# Output_channel.net
KiCad netlist of a schematic drawn in Altium Designer
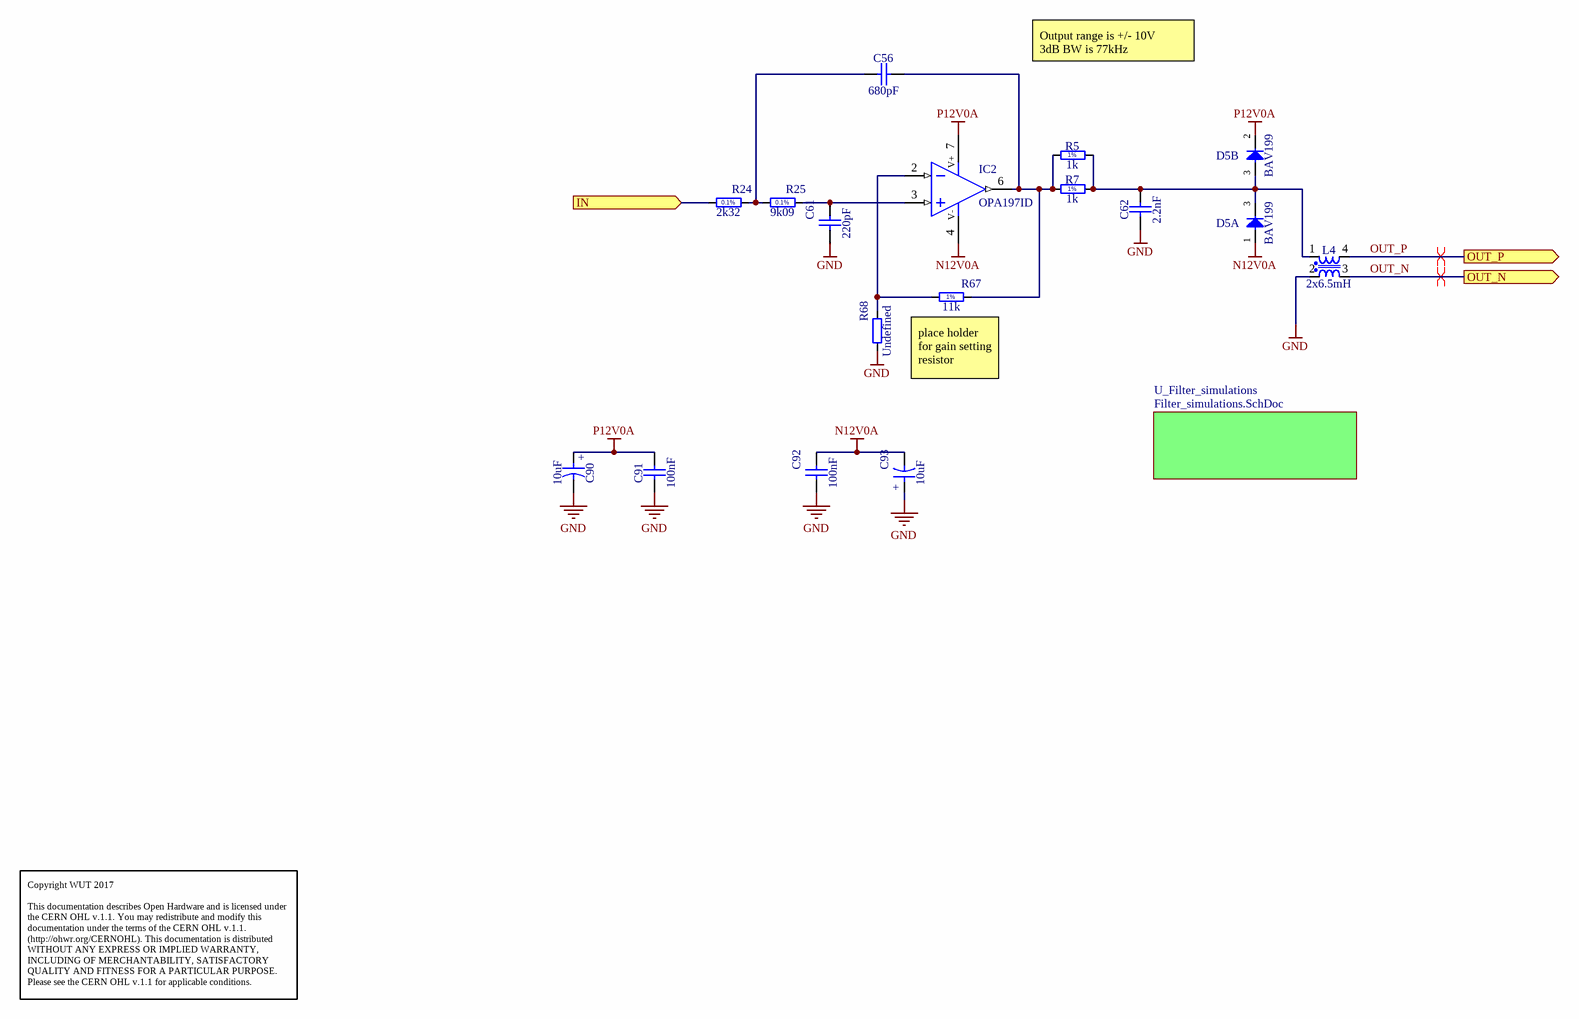
[diagram p0: Output_channel.SchDoc]

(export (version "E")
  (design (tool "Eeschema 10.0.6"))
  (components
    (comp (ref "C56")
      (value "680pF")
      (footprint "CAPC2012X135N")
      (description "Non-polarised capacitor")
      (fields
        (field (name "PART NUMBER") "CC0805_680PF_50V_5%_NP0")
        (field (name "VOLTAGE") "50V")
        (field (name "AUTHOR") "CERN DEM JLC")
      )
      (libsource (lib "Capacitors") (part "Capacitor - non polarized"))
    )
    (comp (ref "C61")
      (value "220pF")
      (footprint "CAPC1608X87N")
      (description "Non-polarised capacitor")
      (fields
        (field (name "PART NUMBER") "CC0603_220PF_50V_5%_NP0")
        (field (name "VOLTAGE") "50V")
        (field (name "AUTHOR") "CERN DEM JLC")
      )
      (libsource (lib "Capacitors") (part "Capacitor - non polarized"))
    )
    (comp (ref "C62")
      (value "2.2nF")
      (footprint "CAPC3216X140N")
      (description "Non-polarised capacitor")
      (fields
        (field (name "PART NUMBER") "CC1206_2.2NF_50V_5%_NP0")
        (field (name "VOLTAGE") "50V")
        (field (name "AUTHOR") "CERN DEM JLC")
      )
      (libsource (lib "Capacitors") (part "Capacitor - non polarized"))
    )
    (comp (ref "C90")
      (value "10uF")
      (footprint "CAPMP3216X180N")
      (description "Polarised capacitor")
      (fields
        (field (name "PART NUMBER") "CTE3216-18_10UF_16V_20%_AVX_TCJ")
        (field (name "VOLTAGE") "16V")
        (field (name "AUTHOR") "CERN DEM JLC")
      )
      (libsource (lib "Capacitors") (part "Capacitor - polarized"))
    )
    (comp (ref "C91")
      (value "100nF")
      (footprint "CAPC1005X55N")
      (description "Non-polarised capacitor")
      (fields
        (field (name "PART NUMBER") "CC0402_100NF_16V_10%_X7R")
        (field (name "VOLTAGE") "16V")
        (field (name "AUTHOR") "CERN DEM JLC")
      )
      (libsource (lib "Capacitors") (part "Capacitor - non polarized"))
    )
    (comp (ref "C92")
      (value "100nF")
      (footprint "CAPC1005X55N")
      (description "Non-polarised capacitor")
      (fields
        (field (name "PART NUMBER") "CC0402_100NF_16V_10%_X7R")
        (field (name "VOLTAGE") "16V")
        (field (name "AUTHOR") "CERN DEM JLC")
      )
      (libsource (lib "Capacitors") (part "Capacitor - non polarized"))
    )
    (comp (ref "C93")
      (value "10uF")
      (footprint "CAPMP3216X180N")
      (description "Polarised capacitor")
      (fields
        (field (name "PART NUMBER") "CTE3216-18_10UF_16V_20%_AVX_TCJ")
        (field (name "VOLTAGE") "16V")
        (field (name "AUTHOR") "CERN DEM JLC")
      )
      (libsource (lib "Capacitors") (part "Capacitor - polarized"))
    )
    (comp (ref "D5")
      (value "BAV199")
      (footprint "SOT95P240X110-3N")
      (description "Serial Diode")
      (fields
        (field (name "VOLTAGE") "75V")
        (field (name "POWER") "250mW")
        (field (name "AUTHOR") "CERN DEM JMW")
      )
      (libsource (lib "ICs And Semiconductors") (part "Diode x2 A1C3_A3C2"))
    )
    (comp (ref "IC2")
      (value "OPA197ID")
      (footprint "SOIC127P600X175-8N")
      (description "36-V, Precision, Rail-to-Rail Input/Output, Low Offset Voltage, Operational Amplifiers")
      (fields (field (name "MANUFACTURER") "TEXAS INSTRUMENTS") (field (name "AUTHOR") "GK"))
      (libsource (lib "LIBRARY_SCH") (part "OA_OPA197"))
    )
    (comp (ref "L4")
      (value "2x6.5mH")
      (footprint "IND_WURTH_WE-SL2")
      (description "Inductor Common Mode")
      (fields
        (field (name "PART NUMBER") "IND_6.5MH_50%_WURTH_WE-SL2-744229")
        (field (name "POWER") "400mA")
        (field (name "AUTHOR") "CERN DEM JLC")
      )
      (libsource (lib "Inductors & Transformers") (part "Inductor Common Mode 1Dot-4 2Dot-3"))
    )
    (comp (ref "R5")
      (value "1k")
      (footprint "RESC1608X55N")
      (description "Resistor - 1%")
      (fields
        (field (name "PART NUMBER") "R0603_1K_1%_0.1W_100PPM")
        (field (name "POWER") "0.1W")
        (field (name "AUTHOR") "CERN DEM JLC")
      )
      (libsource (lib "Resistors") (part "Resistor - 1%"))
    )
    (comp (ref "R7")
      (value "1k")
      (footprint "RESC1608X55N")
      (description "Resistor - 1%")
      (fields
        (field (name "PART NUMBER") "R0603_1K_1%_0.1W_100PPM")
        (field (name "POWER") "0.1W")
        (field (name "AUTHOR") "CERN DEM JLC")
      )
      (libsource (lib "Resistors") (part "Resistor - 1%"))
    )
    (comp (ref "R24")
      (value "2k32")
      (footprint "RESC1608X55N")
      (description "Resistor - 0.1%")
      (fields
        (field (name "PART NUMBER") "R0603_2K32_0.1%_0.063W_10PPM")
        (field (name "POWER") "0.063W")
        (field (name "AUTHOR") "CERN DEM JLC")
      )
      (libsource (lib "Resistors") (part "Resistor - 0.1%"))
    )
    (comp (ref "R25")
      (value "9k09")
      (footprint "RESC1608X55N")
      (description "Resistor - 0.1%")
      (fields
        (field (name "PART NUMBER") "R0603_9K09_0.1%_0.063W_10PPM")
        (field (name "POWER") "0.063W")
        (field (name "AUTHOR") "CERN DEM JLC")
      )
      (libsource (lib "Resistors") (part "Resistor - 0.1%"))
    )
    (comp (ref "R67")
      (value "11k")
      (footprint "RESC1608X55N")
      (description "Resistor - 1%")
      (fields
        (field (name "PART NUMBER") "R0603_11K_1%_0.1W_100PPM")
        (field (name "POWER") "0.1W")
        (field (name "AUTHOR") "CERN DEM JLC")
      )
      (libsource (lib "Resistors") (part "Resistor - 1%"))
    )
    (comp (ref "R68")
      (value "Undefined")
      (footprint "RESC1608X55N")
      (description "Resistor")
      (fields (field (name "PART NUMBER") "R0603_NO-VALUE") (field (name "AUTHOR") "CERN DEM JLC"))
      (libsource (lib "Resistors") (part "Resistor"))
    )
  )
  (nets
    (net (code "1") (name "/IN") (class "Default")
      (node (ref "R24") (pin "1") (pinfunction "1_1") (pintype "passive"))
    )
    (net (code "2") (name "/OUT_N") (class "Default")
      (node (ref "L4") (pin "3") (pinfunction "3_3") (pintype "passive"))
    )
    (net (code "3") (name "/OUT_P") (class "Default")
      (node (ref "L4") (pin "4") (pinfunction "4_4") (pintype "passive"))
    )
    (net (code "4") (name "GND") (class "Default")
      (node (ref "C61") (pin "1") (pinfunction "1_1") (pintype "passive"))
      (node (ref "C62") (pin "1") (pinfunction "1_1") (pintype "passive"))
      (node (ref "C90") (pin "2") (pinfunction "2_2") (pintype "passive"))
      (node (ref "C91") (pin "1") (pinfunction "1_1") (pintype "passive"))
      (node (ref "C92") (pin "1") (pinfunction "1_1") (pintype "passive"))
      (node (ref "C93") (pin "1") (pinfunction "1_1") (pintype "passive"))
      (node (ref "L4") (pin "2") (pinfunction "2_2") (pintype "passive"))
      (node (ref "R68") (pin "1") (pinfunction "1_1") (pintype "passive"))
    )
    (net (code "5") (name "N12V0A") (class "Default")
      (node (ref "C92") (pin "2") (pinfunction "2_2") (pintype "passive"))
      (node (ref "C93") (pin "2") (pinfunction "2_2") (pintype "passive"))
      (node (ref "D5") (pin "1") (pinfunction "A_1") (pintype "passive"))
      (node (ref "IC2") (pin "4") (pinfunction "V-_4") (pintype "power_in"))
    )
    (net (code "6") (name "Net-(C56-Pad1)") (class "Default")
      (node (ref "C56") (pin "1") (pinfunction "1_1") (pintype "passive"))
      (node (ref "R24") (pin "2") (pinfunction "2_2") (pintype "passive"))
      (node (ref "R25") (pin "1") (pinfunction "1_1") (pintype "passive"))
    )
    (net (code "7") (name "Net-(D5A-COMAC)") (class "Default")
      (node (ref "C62") (pin "2") (pinfunction "2_2") (pintype "passive"))
      (node (ref "D5") (pin "3") (pinfunction "COMAC_3") (pintype "passive"))
      (node (ref "L4") (pin "1") (pinfunction "1_1") (pintype "passive"))
      (node (ref "R5") (pin "2") (pinfunction "2_2") (pintype "passive"))
      (node (ref "R7") (pin "2") (pinfunction "2_2") (pintype "passive"))
    )
    (net (code "8") (name "Net-(IC2-IN+)") (class "Default")
      (node (ref "C61") (pin "2") (pinfunction "2_2") (pintype "passive"))
      (node (ref "IC2") (pin "3") (pinfunction "IN+_3") (pintype "input"))
      (node (ref "R25") (pin "2") (pinfunction "2_2") (pintype "passive"))
    )
    (net (code "9") (name "Net-(IC2-IN-)") (class "Default")
      (node (ref "IC2") (pin "2") (pinfunction "IN-_2") (pintype "input"))
      (node (ref "R67") (pin "1") (pinfunction "1_1") (pintype "passive"))
      (node (ref "R68") (pin "2") (pinfunction "2_2") (pintype "passive"))
    )
    (net (code "10") (name "Net-(IC2-OUT)") (class "Default")
      (node (ref "C56") (pin "2") (pinfunction "2_2") (pintype "passive"))
      (node (ref "IC2") (pin "6") (pinfunction "OUT_6") (pintype "output"))
      (node (ref "R5") (pin "1") (pinfunction "1_1") (pintype "passive"))
      (node (ref "R67") (pin "2") (pinfunction "2_2") (pintype "passive"))
      (node (ref "R7") (pin "1") (pinfunction "1_1") (pintype "passive"))
    )
    (net (code "11") (name "P12V0A") (class "Default")
      (node (ref "C90") (pin "1") (pinfunction "1_1") (pintype "passive"))
      (node (ref "C91") (pin "2") (pinfunction "2_2") (pintype "passive"))
      (node (ref "D5") (pin "2") (pinfunction "C_2") (pintype "passive"))
      (node (ref "IC2") (pin "7") (pinfunction "V+_7") (pintype "power_in"))
    )
  )
)
